# LCD_screen.net
KiCad netlist of a schematic drawn in Altium Designer
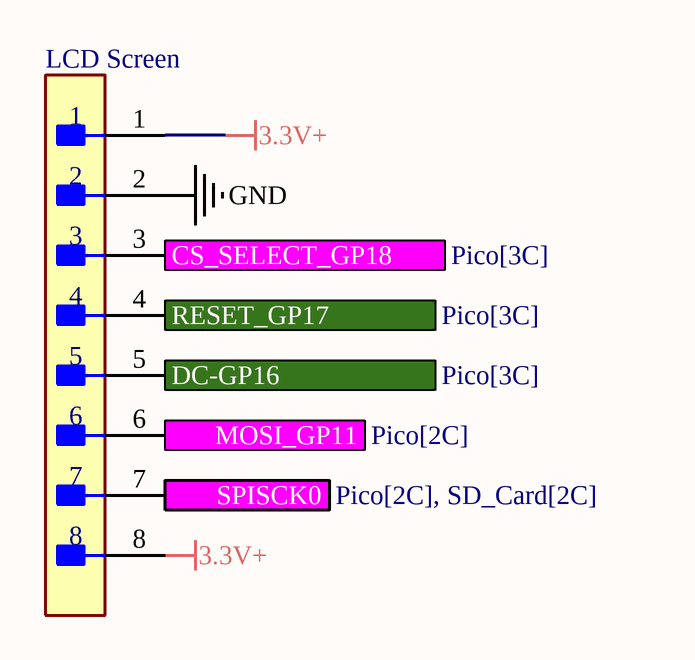
[diagram p0: LCD_screen.SchDoc]

(export (version "E")
  (design (tool "Eeschema 10.0.6"))
  (components
    (comp (ref "LCD Screen")
      (value "LCD")
      (footprint "FP-TSW-108-08-G-S-MFG")
      (description "CONN HEADER VERT 8POS 2.54MM")
      (fields
        (field (name "MANUFACTURER PART NUMBER") "TSW-108-08-G-S")
        (field (name "MANUFACTURER") "Samtec")
      )
      (libsource (lib "Altium Content Vault") (part "99ec2b232beb5d2356d4d77f6a047f0"))
    )
  )
  (nets
    (net (code "6") (name "/CS_SELECT_GP18") (class "Default")
      (node (ref "LCD Screen") (pin "3") (pinfunction "3_3") (pintype "passive"))
    )
    (net (code "7") (name "/DC-GP16") (class "Default")
      (node (ref "LCD Screen") (pin "5") (pinfunction "5_5") (pintype "passive"))
    )
    (net (code "8") (name "/MOSI_GP11") (class "Default")
      (node (ref "LCD Screen") (pin "6") (pinfunction "6_6") (pintype "passive"))
    )
    (net (code "9") (name "/RESET_GP17") (class "Default")
      (node (ref "LCD Screen") (pin "4") (pinfunction "4_4") (pintype "passive"))
    )
    (net (code "10") (name "/SPISCK0") (class "Default")
      (node (ref "LCD Screen") (pin "7") (pinfunction "7_7") (pintype "passive"))
    )
    (net (code "11") (name "3.3V+") (class "Default")
      (node (ref "LCD Screen") (pin "1") (pinfunction "1_1") (pintype "passive"))
      (node (ref "LCD Screen") (pin "8") (pinfunction "8_8") (pintype "passive"))
    )
    (net (code "12") (name "GND") (class "Default")
      (node (ref "LCD Screen") (pin "2") (pinfunction "2_2") (pintype "passive"))
    )
  )
)
